# se2.net
KiCad netlist of a schematic drawn in EAGLE
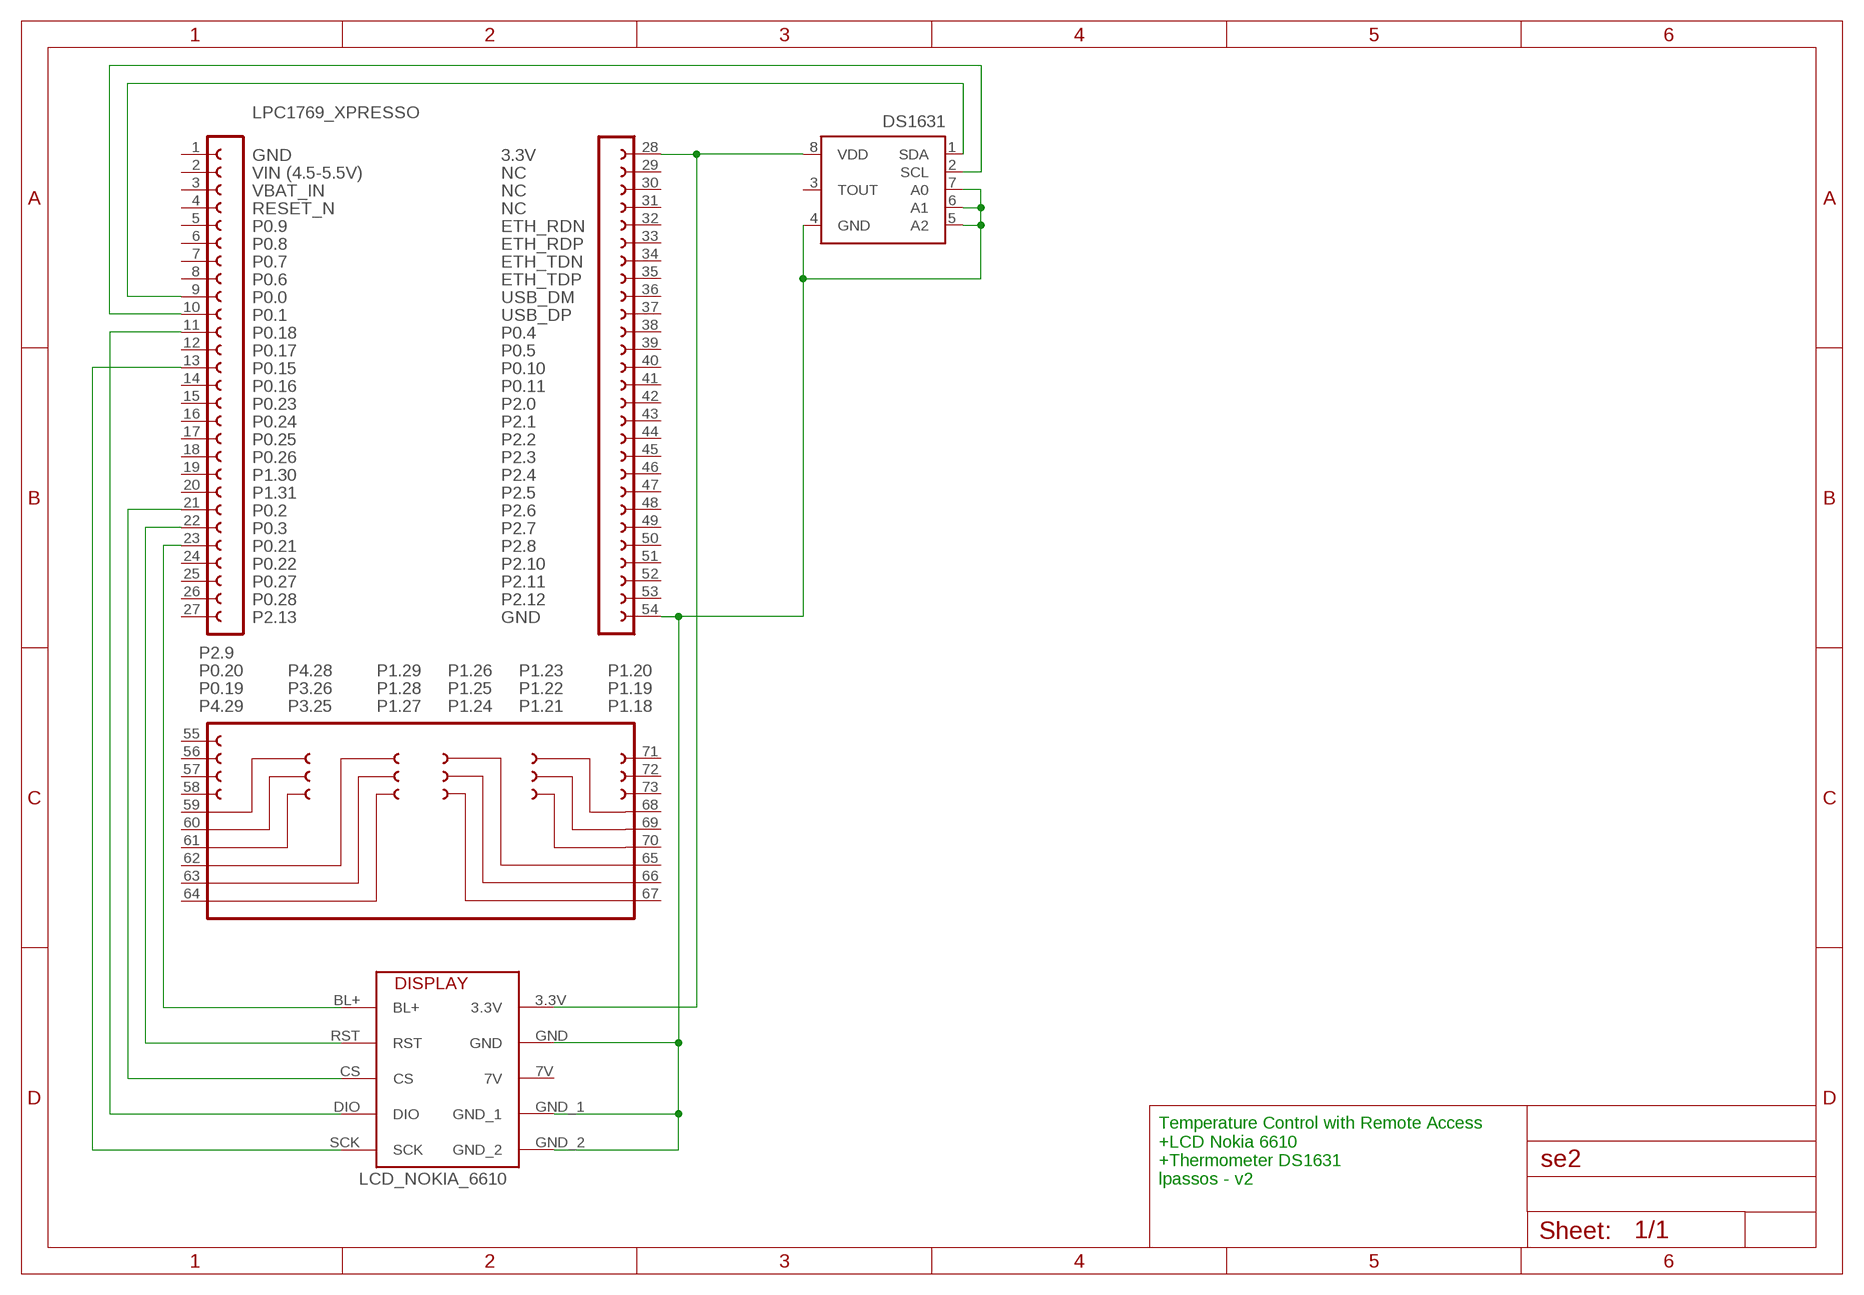
[diagram p0: schematic, sheet 1]

(export (version "E")
  (design (tool "Eeschema 10.0.6"))
  (components
    (comp (ref "DISPLAY")
      (value "NOKIA_LCD_6610")
      (footprint "eagle-import:LCD_NOKIA_6610")
      (libsource (lib "eagle-import") (part "NOKIA_LCD_6610"))
    )
    (comp (ref "DS1631")
      (value "DS1621")
      (footprint "eagle-import:DIL08")
      (libsource (lib "eagle-import") (part "DS1621"))
    )
    (comp (ref "LPC1769_XPRESSO")
      (value "LPCXPRESSO_LPC1769")
      (footprint "eagle-import:LPCXPRESSO_LPC1769")
      (libsource (lib "eagle-import") (part "LPCXPRESSO_LPC1769"))
    )
  )
  (nets
    (net (code "1") (name "Net-(DISPLAY-PadBL+)") (class "Default")
      (node (ref "DISPLAY") (pin "BL+") (pinfunction "BL+_BL+") (pintype "input"))
      (node (ref "LPC1769_XPRESSO") (pin "23") (pinfunction "23_23") (pintype "passive"))
    )
    (net (code "2") (name "Net-(DISPLAY-PadCS)") (class "Default")
      (node (ref "DISPLAY") (pin "CS") (pinfunction "CS_CS") (pintype "bidirectional"))
      (node (ref "LPC1769_XPRESSO") (pin "21") (pinfunction "21_21") (pintype "passive"))
    )
    (net (code "3") (name "Net-(DISPLAY-PadDIO)") (class "Default")
      (node (ref "DISPLAY") (pin "DIO") (pinfunction "DIO_DIO") (pintype "bidirectional"))
      (node (ref "LPC1769_XPRESSO") (pin "11") (pinfunction "11_11") (pintype "passive"))
    )
    (net (code "4") (name "Net-(DISPLAY-PadRST)") (class "Default")
      (node (ref "DISPLAY") (pin "RST") (pinfunction "RST_RST") (pintype "bidirectional"))
      (node (ref "LPC1769_XPRESSO") (pin "22") (pinfunction "22_22") (pintype "passive"))
    )
    (net (code "5") (name "Net-(DISPLAY-PadSCK)") (class "Default")
      (node (ref "DISPLAY") (pin "SCK") (pinfunction "SCK_SCK") (pintype "bidirectional"))
      (node (ref "LPC1769_XPRESSO") (pin "13") (pinfunction "13_13") (pintype "passive"))
    )
    (net (code "6") (name "Net-(DS1631-A0)") (class "Default")
      (node (ref "DISPLAY") (pin "GND") (pinfunction "GND_GND") (pintype "bidirectional"))
      (node (ref "DISPLAY") (pin "GND_1") (pinfunction "GND_1_GND_1") (pintype "bidirectional"))
      (node (ref "DISPLAY") (pin "GND_2") (pinfunction "GND_2_GND_2") (pintype "bidirectional"))
      (node (ref "DS1631") (pin "4") (pinfunction "GND_4") (pintype "power_in"))
      (node (ref "DS1631") (pin "5") (pinfunction "A2_5") (pintype "input"))
      (node (ref "DS1631") (pin "6") (pinfunction "A1_6") (pintype "input"))
      (node (ref "DS1631") (pin "7") (pinfunction "A0_7") (pintype "input"))
      (node (ref "LPC1769_XPRESSO") (pin "54") (pinfunction "54_54") (pintype "passive"))
    )
    (net (code "7") (name "Net-(DS1631-SCL)") (class "Default")
      (node (ref "DS1631") (pin "2") (pinfunction "SCL_2") (pintype "input"))
      (node (ref "LPC1769_XPRESSO") (pin "10") (pinfunction "10_10") (pintype "passive"))
    )
    (net (code "8") (name "Net-(DS1631-SDA)") (class "Default")
      (node (ref "DS1631") (pin "1") (pinfunction "SDA_1") (pintype "bidirectional"))
      (node (ref "LPC1769_XPRESSO") (pin "9") (pinfunction "9_9") (pintype "passive"))
    )
    (net (code "9") (name "Net-(DS1631-VDD)") (class "Default")
      (node (ref "DISPLAY") (pin "3.3V") (pinfunction "3.3V_3.3V") (pintype "bidirectional"))
      (node (ref "DS1631") (pin "8") (pinfunction "VDD_8") (pintype "power_in"))
      (node (ref "LPC1769_XPRESSO") (pin "28") (pinfunction "28_28") (pintype "passive"))
    )
    (net (code "10") (name "unconnected-(DISPLAY-Pad7V)") (class "Default")
      (node (ref "DISPLAY") (pin "7V") (pinfunction "7V_7V") (pintype "bidirectional"))
    )
    (net (code "11") (name "unconnected-(DS1631-TOUT-Pad3)") (class "Default")
      (node (ref "DS1631") (pin "3") (pinfunction "TOUT_3") (pintype "output"))
    )
    (net (code "12") (name "unconnected-(LPC1769_XPRESSO-Pad1)") (class "Default")
      (node (ref "LPC1769_XPRESSO") (pin "1") (pinfunction "1_1") (pintype "passive"))
    )
    (net (code "13") (name "unconnected-(LPC1769_XPRESSO-Pad2)") (class "Default")
      (node (ref "LPC1769_XPRESSO") (pin "2") (pinfunction "2_2") (pintype "passive"))
    )
    (net (code "14") (name "unconnected-(LPC1769_XPRESSO-Pad3)") (class "Default")
      (node (ref "LPC1769_XPRESSO") (pin "3") (pinfunction "3_3") (pintype "passive"))
    )
    (net (code "15") (name "unconnected-(LPC1769_XPRESSO-Pad4)") (class "Default")
      (node (ref "LPC1769_XPRESSO") (pin "4") (pinfunction "4_4") (pintype "passive"))
    )
    (net (code "16") (name "unconnected-(LPC1769_XPRESSO-Pad5)") (class "Default")
      (node (ref "LPC1769_XPRESSO") (pin "5") (pinfunction "5_5") (pintype "passive"))
    )
    (net (code "17") (name "unconnected-(LPC1769_XPRESSO-Pad6)") (class "Default")
      (node (ref "LPC1769_XPRESSO") (pin "6") (pinfunction "6_6") (pintype "passive"))
    )
    (net (code "18") (name "unconnected-(LPC1769_XPRESSO-Pad7)") (class "Default")
      (node (ref "LPC1769_XPRESSO") (pin "7") (pinfunction "7_7") (pintype "passive"))
    )
    (net (code "19") (name "unconnected-(LPC1769_XPRESSO-Pad8)") (class "Default")
      (node (ref "LPC1769_XPRESSO") (pin "8") (pinfunction "8_8") (pintype "passive"))
    )
    (net (code "20") (name "unconnected-(LPC1769_XPRESSO-Pad12)") (class "Default")
      (node (ref "LPC1769_XPRESSO") (pin "12") (pinfunction "12_12") (pintype "passive"))
    )
    (net (code "21") (name "unconnected-(LPC1769_XPRESSO-Pad14)") (class "Default")
      (node (ref "LPC1769_XPRESSO") (pin "14") (pinfunction "14_14") (pintype "passive"))
    )
    (net (code "22") (name "unconnected-(LPC1769_XPRESSO-Pad15)") (class "Default")
      (node (ref "LPC1769_XPRESSO") (pin "15") (pinfunction "15_15") (pintype "passive"))
    )
    (net (code "23") (name "unconnected-(LPC1769_XPRESSO-Pad16)") (class "Default")
      (node (ref "LPC1769_XPRESSO") (pin "16") (pinfunction "16_16") (pintype "passive"))
    )
    (net (code "24") (name "unconnected-(LPC1769_XPRESSO-Pad17)") (class "Default")
      (node (ref "LPC1769_XPRESSO") (pin "17") (pinfunction "17_17") (pintype "passive"))
    )
    (net (code "25") (name "unconnected-(LPC1769_XPRESSO-Pad18)") (class "Default")
      (node (ref "LPC1769_XPRESSO") (pin "18") (pinfunction "18_18") (pintype "passive"))
    )
    (net (code "26") (name "unconnected-(LPC1769_XPRESSO-Pad19)") (class "Default")
      (node (ref "LPC1769_XPRESSO") (pin "19") (pinfunction "19_19") (pintype "passive"))
    )
    (net (code "27") (name "unconnected-(LPC1769_XPRESSO-Pad20)") (class "Default")
      (node (ref "LPC1769_XPRESSO") (pin "20") (pinfunction "20_20") (pintype "passive"))
    )
    (net (code "28") (name "unconnected-(LPC1769_XPRESSO-Pad24)") (class "Default")
      (node (ref "LPC1769_XPRESSO") (pin "24") (pinfunction "24_24") (pintype "passive"))
    )
    (net (code "29") (name "unconnected-(LPC1769_XPRESSO-Pad25)") (class "Default")
      (node (ref "LPC1769_XPRESSO") (pin "25") (pinfunction "25_25") (pintype "passive"))
    )
    (net (code "30") (name "unconnected-(LPC1769_XPRESSO-Pad26)") (class "Default")
      (node (ref "LPC1769_XPRESSO") (pin "26") (pinfunction "26_26") (pintype "passive"))
    )
    (net (code "31") (name "unconnected-(LPC1769_XPRESSO-Pad27)") (class "Default")
      (node (ref "LPC1769_XPRESSO") (pin "27") (pinfunction "27_27") (pintype "passive"))
    )
    (net (code "32") (name "unconnected-(LPC1769_XPRESSO-Pad29)") (class "Default")
      (node (ref "LPC1769_XPRESSO") (pin "29") (pinfunction "29_29") (pintype "passive"))
    )
    (net (code "33") (name "unconnected-(LPC1769_XPRESSO-Pad30)") (class "Default")
      (node (ref "LPC1769_XPRESSO") (pin "30") (pinfunction "30_30") (pintype "passive"))
    )
    (net (code "34") (name "unconnected-(LPC1769_XPRESSO-Pad31)") (class "Default")
      (node (ref "LPC1769_XPRESSO") (pin "31") (pinfunction "31_31") (pintype "passive"))
    )
    (net (code "35") (name "unconnected-(LPC1769_XPRESSO-Pad32)") (class "Default")
      (node (ref "LPC1769_XPRESSO") (pin "32") (pinfunction "32_32") (pintype "passive"))
    )
    (net (code "36") (name "unconnected-(LPC1769_XPRESSO-Pad33)") (class "Default")
      (node (ref "LPC1769_XPRESSO") (pin "33") (pinfunction "33_33") (pintype "passive"))
    )
    (net (code "37") (name "unconnected-(LPC1769_XPRESSO-Pad34)") (class "Default")
      (node (ref "LPC1769_XPRESSO") (pin "34") (pinfunction "34_34") (pintype "passive"))
    )
    (net (code "38") (name "unconnected-(LPC1769_XPRESSO-Pad35)") (class "Default")
      (node (ref "LPC1769_XPRESSO") (pin "35") (pinfunction "35_35") (pintype "passive"))
    )
    (net (code "39") (name "unconnected-(LPC1769_XPRESSO-Pad36)") (class "Default")
      (node (ref "LPC1769_XPRESSO") (pin "36") (pinfunction "36_36") (pintype "passive"))
    )
    (net (code "40") (name "unconnected-(LPC1769_XPRESSO-Pad37)") (class "Default")
      (node (ref "LPC1769_XPRESSO") (pin "37") (pinfunction "37_37") (pintype "passive"))
    )
    (net (code "41") (name "unconnected-(LPC1769_XPRESSO-Pad38)") (class "Default")
      (node (ref "LPC1769_XPRESSO") (pin "38") (pinfunction "38_38") (pintype "passive"))
    )
    (net (code "42") (name "unconnected-(LPC1769_XPRESSO-Pad39)") (class "Default")
      (node (ref "LPC1769_XPRESSO") (pin "39") (pinfunction "39_39") (pintype "passive"))
    )
    (net (code "43") (name "unconnected-(LPC1769_XPRESSO-Pad40)") (class "Default")
      (node (ref "LPC1769_XPRESSO") (pin "40") (pinfunction "40_40") (pintype "passive"))
    )
    (net (code "44") (name "unconnected-(LPC1769_XPRESSO-Pad41)") (class "Default")
      (node (ref "LPC1769_XPRESSO") (pin "41") (pinfunction "41_41") (pintype "passive"))
    )
    (net (code "45") (name "unconnected-(LPC1769_XPRESSO-Pad42)") (class "Default")
      (node (ref "LPC1769_XPRESSO") (pin "42") (pinfunction "42_42") (pintype "passive"))
    )
    (net (code "46") (name "unconnected-(LPC1769_XPRESSO-Pad43)") (class "Default")
      (node (ref "LPC1769_XPRESSO") (pin "43") (pinfunction "43_43") (pintype "passive"))
    )
    (net (code "47") (name "unconnected-(LPC1769_XPRESSO-Pad44)") (class "Default")
      (node (ref "LPC1769_XPRESSO") (pin "44") (pinfunction "44_44") (pintype "passive"))
    )
    (net (code "48") (name "unconnected-(LPC1769_XPRESSO-Pad45)") (class "Default")
      (node (ref "LPC1769_XPRESSO") (pin "45") (pinfunction "45_45") (pintype "passive"))
    )
    (net (code "49") (name "unconnected-(LPC1769_XPRESSO-Pad46)") (class "Default")
      (node (ref "LPC1769_XPRESSO") (pin "46") (pinfunction "46_46") (pintype "passive"))
    )
    (net (code "50") (name "unconnected-(LPC1769_XPRESSO-Pad47)") (class "Default")
      (node (ref "LPC1769_XPRESSO") (pin "47") (pinfunction "47_47") (pintype "passive"))
    )
    (net (code "51") (name "unconnected-(LPC1769_XPRESSO-Pad48)") (class "Default")
      (node (ref "LPC1769_XPRESSO") (pin "48") (pinfunction "48_48") (pintype "passive"))
    )
    (net (code "52") (name "unconnected-(LPC1769_XPRESSO-Pad49)") (class "Default")
      (node (ref "LPC1769_XPRESSO") (pin "49") (pinfunction "49_49") (pintype "passive"))
    )
    (net (code "53") (name "unconnected-(LPC1769_XPRESSO-Pad50)") (class "Default")
      (node (ref "LPC1769_XPRESSO") (pin "50") (pinfunction "50_50") (pintype "passive"))
    )
    (net (code "54") (name "unconnected-(LPC1769_XPRESSO-Pad51)") (class "Default")
      (node (ref "LPC1769_XPRESSO") (pin "51") (pinfunction "51_51") (pintype "passive"))
    )
    (net (code "55") (name "unconnected-(LPC1769_XPRESSO-Pad52)") (class "Default")
      (node (ref "LPC1769_XPRESSO") (pin "52") (pinfunction "52_52") (pintype "passive"))
    )
    (net (code "56") (name "unconnected-(LPC1769_XPRESSO-Pad53)") (class "Default")
      (node (ref "LPC1769_XPRESSO") (pin "53") (pinfunction "53_53") (pintype "passive"))
    )
    (net (code "57") (name "unconnected-(LPC1769_XPRESSO-Pad55)") (class "Default")
      (node (ref "LPC1769_XPRESSO") (pin "55") (pinfunction "55_55") (pintype "passive"))
    )
    (net (code "58") (name "unconnected-(LPC1769_XPRESSO-Pad56)") (class "Default")
      (node (ref "LPC1769_XPRESSO") (pin "56") (pinfunction "56_56") (pintype "passive"))
    )
    (net (code "59") (name "unconnected-(LPC1769_XPRESSO-Pad57)") (class "Default")
      (node (ref "LPC1769_XPRESSO") (pin "57") (pinfunction "57_57") (pintype "passive"))
    )
    (net (code "60") (name "unconnected-(LPC1769_XPRESSO-Pad58)") (class "Default")
      (node (ref "LPC1769_XPRESSO") (pin "58") (pinfunction "58_58") (pintype "passive"))
    )
    (net (code "61") (name "unconnected-(LPC1769_XPRESSO-Pad59)") (class "Default")
      (node (ref "LPC1769_XPRESSO") (pin "59") (pinfunction "59_59") (pintype "passive"))
    )
    (net (code "62") (name "unconnected-(LPC1769_XPRESSO-Pad60)") (class "Default")
      (node (ref "LPC1769_XPRESSO") (pin "60") (pinfunction "60_60") (pintype "passive"))
    )
    (net (code "63") (name "unconnected-(LPC1769_XPRESSO-Pad61)") (class "Default")
      (node (ref "LPC1769_XPRESSO") (pin "61") (pinfunction "61_61") (pintype "passive"))
    )
    (net (code "64") (name "unconnected-(LPC1769_XPRESSO-Pad62)") (class "Default")
      (node (ref "LPC1769_XPRESSO") (pin "62") (pinfunction "62_62") (pintype "passive"))
    )
    (net (code "65") (name "unconnected-(LPC1769_XPRESSO-Pad63)") (class "Default")
      (node (ref "LPC1769_XPRESSO") (pin "63") (pinfunction "63_63") (pintype "passive"))
    )
    (net (code "66") (name "unconnected-(LPC1769_XPRESSO-Pad64)") (class "Default")
      (node (ref "LPC1769_XPRESSO") (pin "64") (pinfunction "64_64") (pintype "passive"))
    )
    (net (code "67") (name "unconnected-(LPC1769_XPRESSO-Pad65)") (class "Default")
      (node (ref "LPC1769_XPRESSO") (pin "65") (pinfunction "65_65") (pintype "passive"))
    )
    (net (code "68") (name "unconnected-(LPC1769_XPRESSO-Pad66)") (class "Default")
      (node (ref "LPC1769_XPRESSO") (pin "66") (pinfunction "66_66") (pintype "passive"))
    )
    (net (code "69") (name "unconnected-(LPC1769_XPRESSO-Pad67)") (class "Default")
      (node (ref "LPC1769_XPRESSO") (pin "67") (pinfunction "67_67") (pintype "passive"))
    )
    (net (code "70") (name "unconnected-(LPC1769_XPRESSO-Pad68)") (class "Default")
      (node (ref "LPC1769_XPRESSO") (pin "68") (pinfunction "68_68") (pintype "passive"))
    )
    (net (code "71") (name "unconnected-(LPC1769_XPRESSO-Pad69)") (class "Default")
      (node (ref "LPC1769_XPRESSO") (pin "69") (pinfunction "69_69") (pintype "passive"))
    )
    (net (code "72") (name "unconnected-(LPC1769_XPRESSO-Pad70)") (class "Default")
      (node (ref "LPC1769_XPRESSO") (pin "70") (pinfunction "70_70") (pintype "passive"))
    )
    (net (code "73") (name "unconnected-(LPC1769_XPRESSO-Pad71)") (class "Default")
      (node (ref "LPC1769_XPRESSO") (pin "71") (pinfunction "71_71") (pintype "passive"))
    )
    (net (code "74") (name "unconnected-(LPC1769_XPRESSO-Pad72)") (class "Default")
      (node (ref "LPC1769_XPRESSO") (pin "72") (pinfunction "72_72") (pintype "passive"))
    )
    (net (code "75") (name "unconnected-(LPC1769_XPRESSO-Pad73)") (class "Default")
      (node (ref "LPC1769_XPRESSO") (pin "73") (pinfunction "73_73") (pintype "passive"))
    )
  )
)
